# ESP32Board.net
KiCad netlist of a schematic drawn in EAGLE
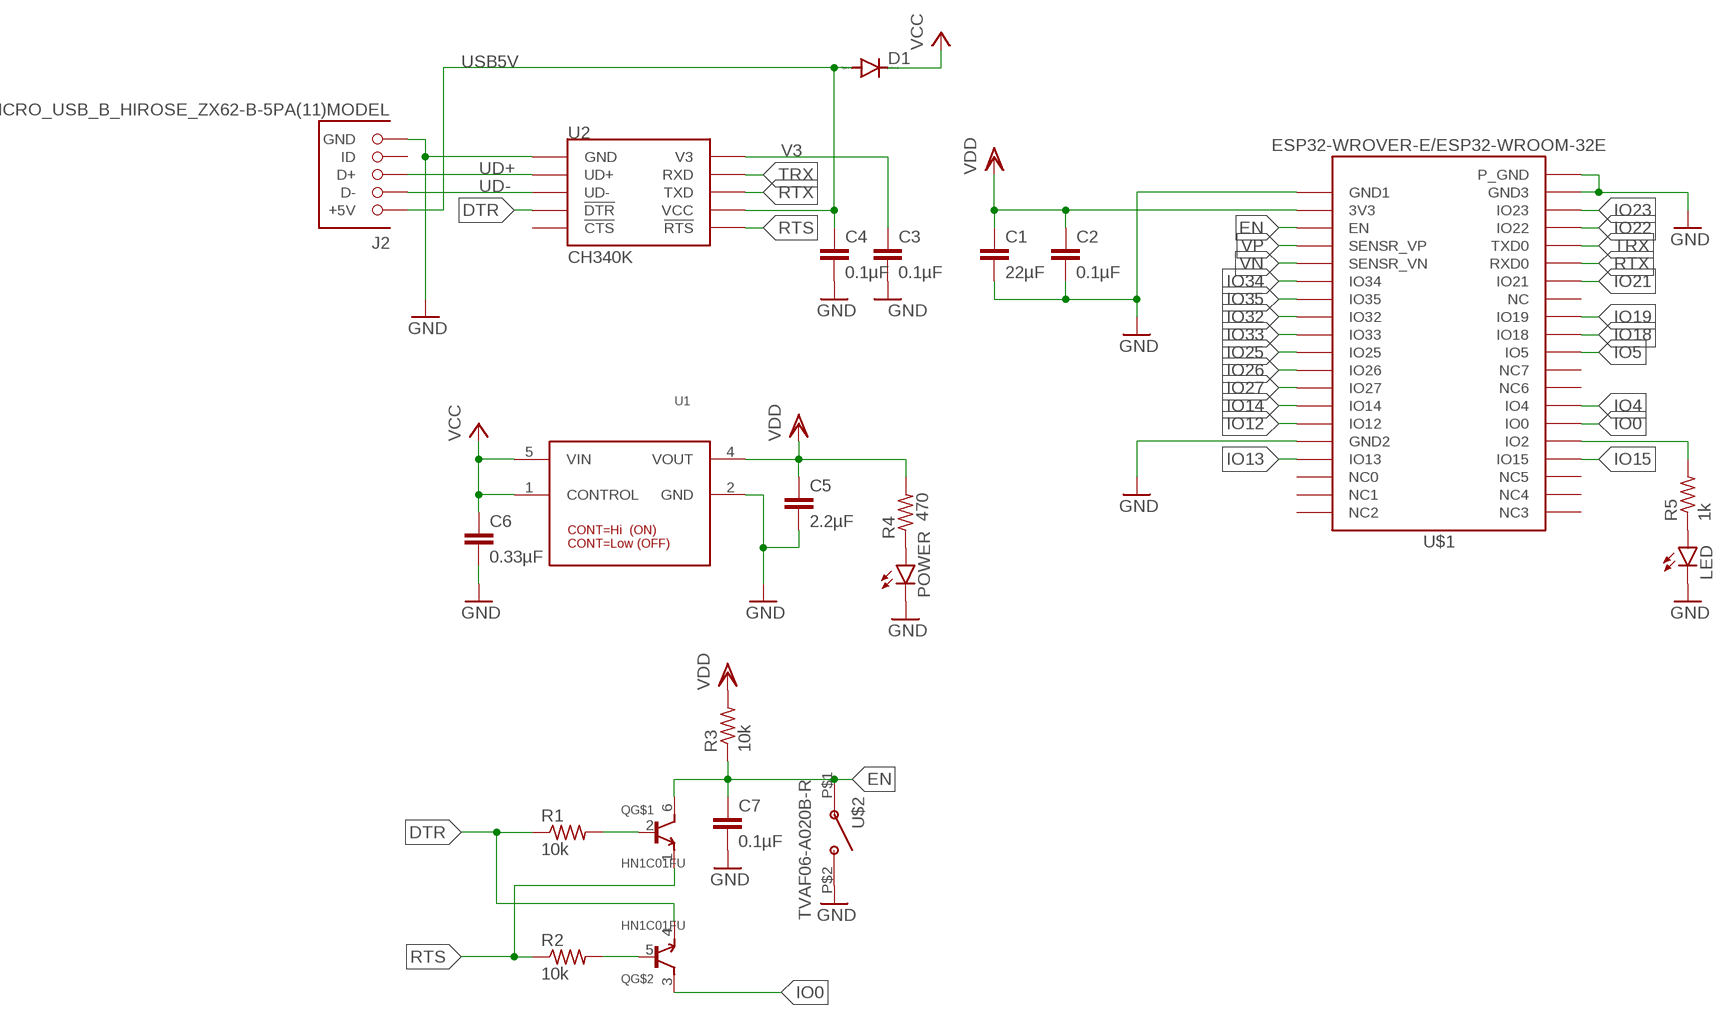
[diagram p0: schematic, sheet 1]

(export (version "E")
  (design (tool "Eeschema 10.0.6"))
  (components
    (comp (ref "C1")
      (value "22µF")
      (footprint "eagle-import:C0603K")
      (libsource (lib "eagle-import") (part "C-EUC0603K"))
    )
    (comp (ref "C2")
      (value "0.1µF")
      (footprint "eagle-import:C0603K")
      (libsource (lib "eagle-import") (part "C-EUC0603K"))
    )
    (comp (ref "C3")
      (value "0.1µF")
      (footprint "eagle-import:C0603K")
      (libsource (lib "eagle-import") (part "C-EUC0603K"))
    )
    (comp (ref "C4")
      (value "0.1µF")
      (footprint "eagle-import:C0603K")
      (libsource (lib "eagle-import") (part "C-EUC0603K"))
    )
    (comp (ref "C5")
      (value "2.2µF")
      (footprint "eagle-import:C0603K")
      (libsource (lib "eagle-import") (part "C-EUC0603K"))
    )
    (comp (ref "C6")
      (value "0.33µF")
      (footprint "eagle-import:C0603K")
      (libsource (lib "eagle-import") (part "C-EUC0603K"))
    )
    (comp (ref "C7")
      (value "0.1µF")
      (footprint "eagle-import:C0603K")
      (libsource (lib "eagle-import") (part "C-EUC0603K"))
    )
    (comp (ref "D1")
      (value "DIODE-SOD123")
      (footprint "eagle-import:SOD123")
      (libsource (lib "eagle-import") (part "DIODE-SOD123"))
    )
    (comp (ref "J2")
      (value "MICRO_USB_B_HIROSE_ZX62-B-5PA(11)MODEL")
      (footprint "eagle-import:GHI-CONNECTORS_10118192-0001LF(MICRO-USB-B-AMPHENOL-FCI)")
      (libsource (lib "eagle-import") (part "MICRO_USB_B_HIROSE_ZX62-B-5PA(11)MODEL"))
    )
    (comp (ref "LED")
      (value "LEDCHIPLED_0603")
      (footprint "eagle-import:CHIPLED_0603")
      (libsource (lib "eagle-import") (part "LEDCHIPLED_0603"))
    )
    (comp (ref "POWER")
      (value "LEDCHIPLED_0603")
      (footprint "eagle-import:CHIPLED_0603")
      (libsource (lib "eagle-import") (part "LEDCHIPLED_0603"))
    )
    (comp (ref "Q")
      (value "HN1C01FU")
      (footprint "eagle-import:SOT-363")
      (libsource (lib "eagle-import") (part "HN1C01FU"))
    )
    (comp (ref "R1")
      (value "10k")
      (footprint "eagle-import:R0603")
      (libsource (lib "eagle-import") (part "R-US_R0603"))
    )
    (comp (ref "R2")
      (value "10k")
      (footprint "eagle-import:R0603")
      (libsource (lib "eagle-import") (part "R-US_R0603"))
    )
    (comp (ref "R3")
      (value "10k")
      (footprint "eagle-import:R0603")
      (libsource (lib "eagle-import") (part "R-US_R0603"))
    )
    (comp (ref "R4")
      (value "470")
      (footprint "eagle-import:R0603")
      (libsource (lib "eagle-import") (part "R-US_R0603"))
    )
    (comp (ref "R5")
      (value "1k")
      (footprint "eagle-import:R0603")
      (libsource (lib "eagle-import") (part "R-US_R0603"))
    )
    (comp (ref "U$1")
      (value "ESP32-WROVER-E/ESP32-WROOM-32E")
      (footprint "eagle-import:ESP32-WROVER-E_ESP32-WROOM-32E")
      (libsource (lib "eagle-import") (part "ESP32-WROVER-E/ESP32-WROOM-32E"))
    )
    (comp (ref "U$2")
      (value "TVAF06-A020B-R")
      (footprint "eagle-import:TVAF06-A020B-R")
      (libsource (lib "eagle-import") (part "TVAF06-A020B-R"))
    )
    (comp (ref "U1")
      (value "I-10673_NJM2884U1-33")
      (footprint "eagle-import:NJM2884U1-33")
      (libsource (lib "eagle-import") (part "I-10673_NJM2884U1-33"))
    )
    (comp (ref "U2")
      (value "CH340K")
      (footprint "eagle-import:ESSOP-10")
      (libsource (lib "eagle-import") (part "CH340K"))
    )
  )
  (nets
    (net (code "1") (name "/UD+") (class "Default")
      (node (ref "J2") (pin "D+") (pinfunction "D+_D+") (pintype "bidirectional"))
      (node (ref "U2") (pin "P1") (pinfunction "UD+_P1") (pintype "bidirectional"))
    )
    (net (code "2") (name "/UD-") (class "Default")
      (node (ref "J2") (pin "D-") (pinfunction "D-_D-") (pintype "bidirectional"))
      (node (ref "U2") (pin "P2") (pinfunction "UD-_P2") (pintype "bidirectional"))
    )
    (net (code "3") (name "/USB5V") (class "Default")
      (node (ref "C4") (pin "1") (pinfunction "1_1") (pintype "passive"))
      (node (ref "D1") (pin "A") (pinfunction "A_A") (pintype "passive"))
      (node (ref "J2") (pin "VBUS") (pinfunction "+5V_VBUS") (pintype "bidirectional"))
      (node (ref "U2") (pin "P7") (pinfunction "VCC_P7") (pintype "power_in"))
    )
    (net (code "4") (name "/V3") (class "Default")
      (node (ref "C3") (pin "1") (pinfunction "1_1") (pintype "passive"))
      (node (ref "U2") (pin "P10") (pinfunction "V3_P10") (pintype "power_in"))
    )
    (net (code "5") (name "DTR") (class "Default")
      (node (ref "Q") (pin "4") (pinfunction "E_4") (pintype "bidirectional"))
      (node (ref "R1") (pin "1") (pinfunction "1_1") (pintype "passive"))
      (node (ref "U2") (pin "P4") (pinfunction "~{DTR}_P4") (pintype "bidirectional"))
    )
    (net (code "6") (name "EN") (class "Default")
      (node (ref "C7") (pin "1") (pinfunction "1_1") (pintype "passive"))
      (node (ref "Q") (pin "6") (pinfunction "C_6") (pintype "bidirectional"))
      (node (ref "R3") (pin "1") (pinfunction "1_1") (pintype "passive"))
      (node (ref "U$1") (pin "EN") (pinfunction "EN_EN") (pintype "bidirectional"))
      (node (ref "U$2") (pin "P$1") (pinfunction "A_P$1") (pintype "bidirectional"))
    )
    (net (code "7") (name "GND") (class "Default")
      (node (ref "C1") (pin "2") (pinfunction "2_2") (pintype "passive"))
      (node (ref "C2") (pin "2") (pinfunction "2_2") (pintype "passive"))
      (node (ref "C3") (pin "2") (pinfunction "2_2") (pintype "passive"))
      (node (ref "C4") (pin "2") (pinfunction "2_2") (pintype "passive"))
      (node (ref "C5") (pin "2") (pinfunction "2_2") (pintype "passive"))
      (node (ref "C6") (pin "2") (pinfunction "2_2") (pintype "passive"))
      (node (ref "C7") (pin "2") (pinfunction "2_2") (pintype "passive"))
      (node (ref "J2") (pin "CGND1") (pinfunction "GND_CGND1") (pintype "bidirectional"))
      (node (ref "J2") (pin "CGND2") (pinfunction "GND_CGND2") (pintype "bidirectional"))
      (node (ref "J2") (pin "CGND3") (pinfunction "GND_CGND3") (pintype "bidirectional"))
      (node (ref "J2") (pin "CGND4") (pinfunction "GND_CGND4") (pintype "bidirectional"))
      (node (ref "J2") (pin "CGND5") (pinfunction "GND_CGND5") (pintype "bidirectional"))
      (node (ref "J2") (pin "CGND6") (pinfunction "GND_CGND6") (pintype "bidirectional"))
      (node (ref "J2") (pin "GND") (pinfunction "GND_GND") (pintype "bidirectional"))
      (node (ref "LED") (pin "C") (pinfunction "C_C") (pintype "passive"))
      (node (ref "POWER") (pin "C") (pinfunction "C_C") (pintype "passive"))
      (node (ref "U$1") (pin "GND1") (pinfunction "GND1_GND1") (pintype "power_in"))
      (node (ref "U$1") (pin "GND2") (pinfunction "GND2_GND2") (pintype "power_in"))
      (node (ref "U$1") (pin "GND2'") (pinfunction "GND2_GND2'") (pintype "power_in"))
      (node (ref "U$1") (pin "GND3") (pinfunction "GND3_GND3") (pintype "power_in"))
      (node (ref "U$1") (pin "P_GND") (pinfunction "P_GND_P_GND") (pintype "power_in"))
      (node (ref "U$2") (pin "P$2") (pinfunction "B_P$2") (pintype "bidirectional"))
      (node (ref "U1") (pin "2") (pinfunction "GND_2") (pintype "bidirectional"))
      (node (ref "U2") (pin "P0") (pinfunction "GND_P0") (pintype "power_in"))
      (node (ref "U2") (pin "P3") (pinfunction "GND_P3") (pintype "power_in"))
    )
    (net (code "8") (name "IO0") (class "Default")
      (node (ref "Q") (pin "3") (pinfunction "C_3") (pintype "bidirectional"))
      (node (ref "U$1") (pin "IO0") (pinfunction "IO0_IO0") (pintype "bidirectional"))
    )
    (net (code "9") (name "IO4") (class "Default")
      (node (ref "U$1") (pin "IO4") (pinfunction "IO4_IO4") (pintype "bidirectional"))
    )
    (net (code "10") (name "IO5") (class "Default")
      (node (ref "U$1") (pin "IO5") (pinfunction "IO5_IO5") (pintype "bidirectional"))
    )
    (net (code "11") (name "IO12") (class "Default")
      (node (ref "U$1") (pin "IO12") (pinfunction "IO12_IO12") (pintype "bidirectional"))
    )
    (net (code "12") (name "IO13") (class "Default")
      (node (ref "U$1") (pin "IO13") (pinfunction "IO13_IO13") (pintype "bidirectional"))
      (node (ref "U$1") (pin "IO13'") (pinfunction "IO13_IO13'") (pintype "bidirectional"))
    )
    (net (code "13") (name "IO14") (class "Default")
      (node (ref "U$1") (pin "IO14") (pinfunction "IO14_IO14") (pintype "bidirectional"))
    )
    (net (code "14") (name "IO15") (class "Default")
      (node (ref "U$1") (pin "IO15") (pinfunction "IO15_IO15") (pintype "bidirectional"))
      (node (ref "U$1") (pin "IO15'") (pinfunction "IO15_IO15'") (pintype "bidirectional"))
    )
    (net (code "15") (name "IO18") (class "Default")
      (node (ref "U$1") (pin "IO18") (pinfunction "IO18_IO18") (pintype "bidirectional"))
    )
    (net (code "16") (name "IO19") (class "Default")
      (node (ref "U$1") (pin "IO19") (pinfunction "IO19_IO19") (pintype "bidirectional"))
    )
    (net (code "17") (name "IO21") (class "Default")
      (node (ref "U$1") (pin "IO21") (pinfunction "IO21_IO21") (pintype "bidirectional"))
    )
    (net (code "18") (name "IO22") (class "Default")
      (node (ref "U$1") (pin "IO22") (pinfunction "IO22_IO22") (pintype "bidirectional"))
    )
    (net (code "19") (name "IO23") (class "Default")
      (node (ref "U$1") (pin "IO23") (pinfunction "IO23_IO23") (pintype "bidirectional"))
    )
    (net (code "20") (name "IO25") (class "Default")
      (node (ref "U$1") (pin "IO25") (pinfunction "IO25_IO25") (pintype "bidirectional"))
    )
    (net (code "21") (name "IO26") (class "Default")
      (node (ref "U$1") (pin "IO26") (pinfunction "IO26_IO26") (pintype "bidirectional"))
    )
    (net (code "22") (name "IO27") (class "Default")
      (node (ref "U$1") (pin "IO27") (pinfunction "IO27_IO27") (pintype "bidirectional"))
    )
    (net (code "23") (name "IO32") (class "Default")
      (node (ref "U$1") (pin "IO32") (pinfunction "IO32_IO32") (pintype "bidirectional"))
    )
    (net (code "24") (name "IO33") (class "Default")
      (node (ref "U$1") (pin "IO33") (pinfunction "IO33_IO33") (pintype "bidirectional"))
    )
    (net (code "25") (name "IO34") (class "Default")
      (node (ref "U$1") (pin "IO34") (pinfunction "IO34_IO34") (pintype "bidirectional"))
    )
    (net (code "26") (name "IO35") (class "Default")
      (node (ref "U$1") (pin "IO35") (pinfunction "IO35_IO35") (pintype "bidirectional"))
    )
    (net (code "27") (name "Net-(LED-PadA)") (class "Default")
      (node (ref "LED") (pin "A") (pinfunction "A_A") (pintype "passive"))
      (node (ref "R5") (pin "1") (pinfunction "1_1") (pintype "passive"))
    )
    (net (code "28") (name "Net-(POWER-PadA)") (class "Default")
      (node (ref "POWER") (pin "A") (pinfunction "A_A") (pintype "passive"))
      (node (ref "R4") (pin "1") (pinfunction "1_1") (pintype "passive"))
    )
    (net (code "29") (name "Net-(QA-B)") (class "Default")
      (node (ref "Q") (pin "2") (pinfunction "B_2") (pintype "bidirectional"))
      (node (ref "R1") (pin "2") (pinfunction "2_2") (pintype "passive"))
    )
    (net (code "30") (name "Net-(QB-B)") (class "Default")
      (node (ref "Q") (pin "5") (pinfunction "B_5") (pintype "bidirectional"))
      (node (ref "R2") (pin "2") (pinfunction "2_2") (pintype "passive"))
    )
    (net (code "31") (name "Net-(R5-Pad2)") (class "Default")
      (node (ref "R5") (pin "2") (pinfunction "2_2") (pintype "passive"))
      (node (ref "U$1") (pin "IO2") (pinfunction "IO2_IO2") (pintype "bidirectional"))
      (node (ref "U$1") (pin "IO2'") (pinfunction "IO2_IO2'") (pintype "bidirectional"))
    )
    (net (code "32") (name "RTS") (class "Default")
      (node (ref "Q") (pin "1") (pinfunction "E_1") (pintype "bidirectional"))
      (node (ref "R2") (pin "1") (pinfunction "1_1") (pintype "passive"))
      (node (ref "U2") (pin "P6") (pinfunction "~{RTS}_P6") (pintype "bidirectional"))
    )
    (net (code "33") (name "RTX") (class "Default")
      (node (ref "U$1") (pin "RXD0") (pinfunction "RXD0_RXD0") (pintype "bidirectional"))
      (node (ref "U2") (pin "P8") (pinfunction "TXD_P8") (pintype "bidirectional"))
    )
    (net (code "34") (name "TRX") (class "Default")
      (node (ref "U$1") (pin "TXD0") (pinfunction "TXD0_TXD0") (pintype "bidirectional"))
      (node (ref "U2") (pin "P9") (pinfunction "RXD_P9") (pintype "bidirectional"))
    )
    (net (code "35") (name "VCC") (class "Default")
      (node (ref "C6") (pin "1") (pinfunction "1_1") (pintype "passive"))
      (node (ref "D1") (pin "C") (pinfunction "C_C") (pintype "passive"))
      (node (ref "U1") (pin "1") (pinfunction "CONTROL_1") (pintype "bidirectional"))
      (node (ref "U1") (pin "5") (pinfunction "VIN_5") (pintype "bidirectional"))
    )
    (net (code "36") (name "VDD") (class "Default")
      (node (ref "C1") (pin "1") (pinfunction "1_1") (pintype "passive"))
      (node (ref "C2") (pin "1") (pinfunction "1_1") (pintype "passive"))
      (node (ref "C5") (pin "1") (pinfunction "1_1") (pintype "passive"))
      (node (ref "R3") (pin "2") (pinfunction "2_2") (pintype "passive"))
      (node (ref "R4") (pin "2") (pinfunction "2_2") (pintype "passive"))
      (node (ref "U$1") (pin "3V3") (pinfunction "3V3_3V3") (pintype "power_in"))
      (node (ref "U1") (pin "4") (pinfunction "VOUT_4") (pintype "bidirectional"))
    )
    (net (code "37") (name "VN") (class "Default")
      (node (ref "U$1") (pin "SENSOR_VN") (pinfunction "SENSR_VN_SENSOR_VN") (pintype "bidirectional"))
    )
    (net (code "38") (name "VP") (class "Default")
      (node (ref "U$1") (pin "SENSOR_VP") (pinfunction "SENSR_VP_SENSOR_VP") (pintype "bidirectional"))
    )
    (net (code "39") (name "unconnected-(J2-PadID)") (class "Default")
      (node (ref "J2") (pin "ID") (pinfunction "ID_ID") (pintype "bidirectional"))
    )
    (net (code "40") (name "unconnected-(U$1-NC0-PadNC0')") (class "Default")
      (node (ref "U$1") (pin "NC0'") (pinfunction "NC0_NC0'") (pintype "no_connect"))
    )
    (net (code "41") (name "unconnected-(U$1-NC1-PadNC1')") (class "Default")
      (node (ref "U$1") (pin "NC1'") (pinfunction "NC1_NC1'") (pintype "no_connect"))
    )
    (net (code "42") (name "unconnected-(U$1-NC2-PadNC2')") (class "Default")
      (node (ref "U$1") (pin "NC2'") (pinfunction "NC2_NC2'") (pintype "no_connect"))
    )
    (net (code "43") (name "unconnected-(U$1-NC3-PadNC3')") (class "Default")
      (node (ref "U$1") (pin "NC3'") (pinfunction "NC3_NC3'") (pintype "no_connect"))
    )
    (net (code "44") (name "unconnected-(U$1-NC4-PadNC4')") (class "Default")
      (node (ref "U$1") (pin "NC4'") (pinfunction "NC4_NC4'") (pintype "no_connect"))
    )
    (net (code "45") (name "unconnected-(U$1-NC5-PadNC5')") (class "Default")
      (node (ref "U$1") (pin "NC5'") (pinfunction "NC5_NC5'") (pintype "no_connect"))
    )
    (net (code "46") (name "unconnected-(U$1-NC6-PadIO16)") (class "Default")
      (node (ref "U$1") (pin "IO16") (pinfunction "NC6_IO16") (pintype "no_connect"))
    )
    (net (code "47") (name "unconnected-(U$1-NC7-PadIO17)") (class "Default")
      (node (ref "U$1") (pin "IO17") (pinfunction "NC7_IO17") (pintype "no_connect"))
    )
    (net (code "48") (name "unconnected-(U$1-PadNC)") (class "Default")
      (node (ref "U$1") (pin "NC") (pinfunction "NC_NC") (pintype "no_connect"))
    )
    (net (code "49") (name "unconnected-(U$1-PadNC0)") (class "Default")
      (node (ref "U$1") (pin "NC0") (pinfunction "NC0_NC0") (pintype "no_connect"))
    )
    (net (code "50") (name "unconnected-(U$1-PadNC1)") (class "Default")
      (node (ref "U$1") (pin "NC1") (pinfunction "NC1_NC1") (pintype "no_connect"))
    )
    (net (code "51") (name "unconnected-(U$1-PadNC2)") (class "Default")
      (node (ref "U$1") (pin "NC2") (pinfunction "NC2_NC2") (pintype "no_connect"))
    )
    (net (code "52") (name "unconnected-(U$1-PadNC3)") (class "Default")
      (node (ref "U$1") (pin "NC3") (pinfunction "NC3_NC3") (pintype "no_connect"))
    )
    (net (code "53") (name "unconnected-(U$1-PadNC4)") (class "Default")
      (node (ref "U$1") (pin "NC4") (pinfunction "NC4_NC4") (pintype "no_connect"))
    )
    (net (code "54") (name "unconnected-(U$1-PadNC5)") (class "Default")
      (node (ref "U$1") (pin "NC5") (pinfunction "NC5_NC5") (pintype "no_connect"))
    )
    (net (code "55") (name "unconnected-(U2-~{CTS}-PadP5)") (class "Default")
      (node (ref "U2") (pin "P5") (pinfunction "~{CTS}_P5") (pintype "bidirectional"))
    )
  )
)
